# LooRollSensorTop.net
KiCad netlist of a schematic drawn in EAGLE
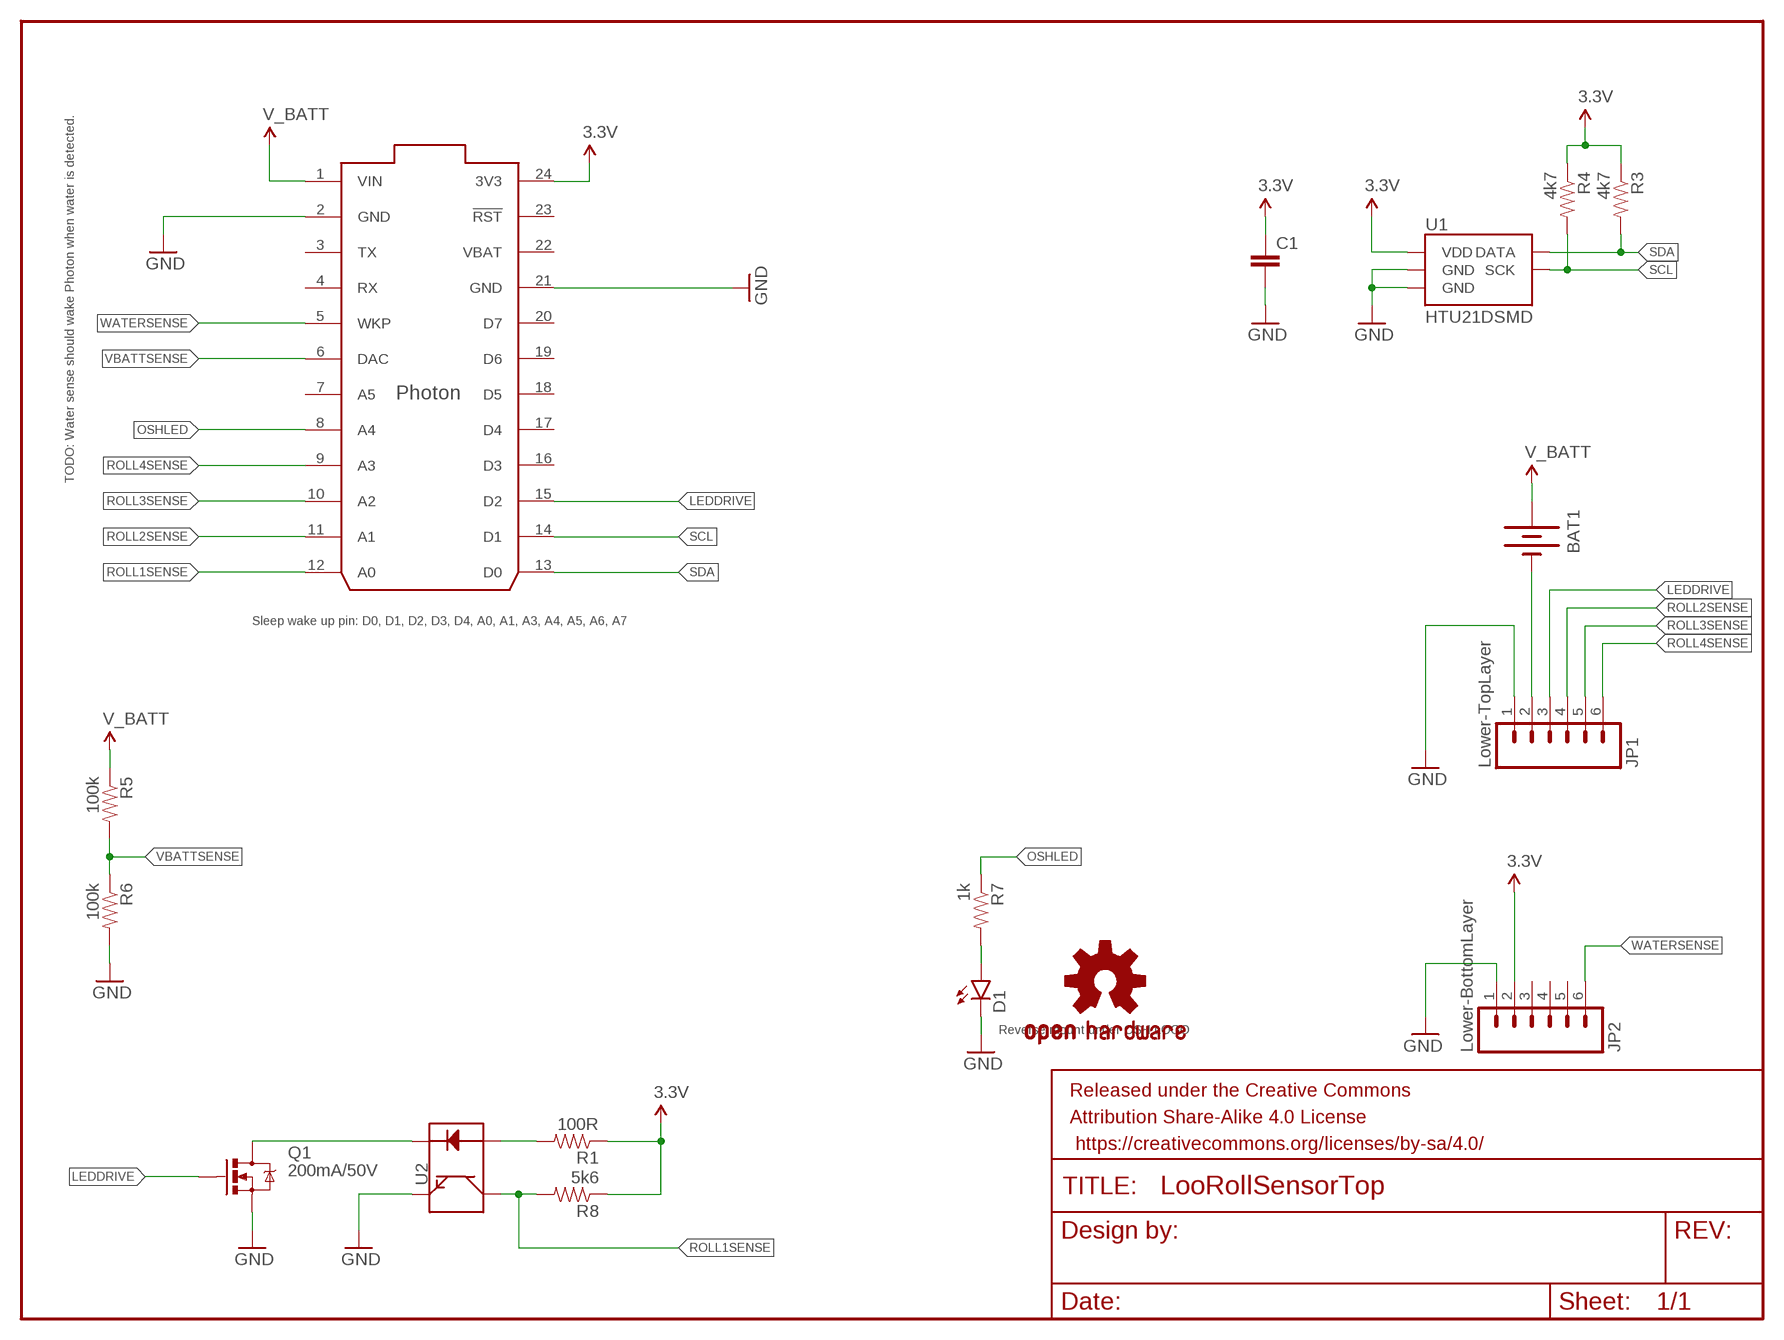
[diagram p0: schematic, sheet 1]

(export (version "E")
  (design (tool "Eeschema 10.0.6"))
  (components
    (comp (ref "BAT1")
      (value "BATTERYAA-PANEL")
      (footprint "eagle-import:BATTERY-AA-PANEL")
      (libsource (lib "eagle-import") (part "BATTERYAA-PANEL"))
    )
    (comp (ref "C1")
      (value "CAP0805")
      (footprint "eagle-import:0805")
      (libsource (lib "eagle-import") (part "CAP0805"))
    )
    (comp (ref "D1")
      (value "LED1206-BOTTOM")
      (footprint "eagle-import:LED-1206-BOTTOM")
      (libsource (lib "eagle-import") (part "LED1206-BOTTOM"))
    )
    (comp (ref "FRAME1")
      (value "FRAME-LETTER")
      (footprint "eagle-import:CREATIVE_COMMONS")
      (libsource (lib "eagle-import") (part "FRAME-LETTER"))
    )
    (comp (ref "JP1")
      (value "Lower-TopLayer")
      (footprint "eagle-import:1X06-SMD_EDGE")
      (libsource (lib "eagle-import") (part "M061X06-SMD-EDGE-SOLDERLINK1X06-SMD-EDGE-SOLDERLINK"))
    )
    (comp (ref "JP2")
      (value "Lower-BottomLayer")
      (footprint "eagle-import:1X06-SMD_EDGE")
      (libsource (lib "eagle-import") (part "M061X06-SMD-EDGE-SOLDERLINK1X06-SMD-EDGE-SOLDERLINK"))
    )
    (comp (ref "LOGO1")
      (value "OSHW-LOGOM")
      (footprint "eagle-import:OSHW-LOGO-M")
      (libsource (lib "eagle-import") (part "OSHW-LOGOM"))
    )
    (comp (ref "Q1")
      (value "200mA/50V")
      (footprint "eagle-import:SOT23-3")
      (libsource (lib "eagle-import") (part "MOSFET-NCHANNELBSS138"))
    )
    (comp (ref "R1")
      (value "100R")
      (footprint "eagle-import:1206")
      (libsource (lib "eagle-import") (part "RESISTOR1206"))
    )
    (comp (ref "R3")
      (value "4k7")
      (footprint "eagle-import:1206")
      (libsource (lib "eagle-import") (part "RESISTOR1206"))
    )
    (comp (ref "R4")
      (value "4k7")
      (footprint "eagle-import:1206")
      (libsource (lib "eagle-import") (part "RESISTOR1206"))
    )
    (comp (ref "R5")
      (value "100k")
      (footprint "eagle-import:1206")
      (libsource (lib "eagle-import") (part "RESISTOR1206"))
    )
    (comp (ref "R6")
      (value "100k")
      (footprint "eagle-import:1206")
      (libsource (lib "eagle-import") (part "RESISTOR1206"))
    )
    (comp (ref "R7")
      (value "1k")
      (footprint "eagle-import:1206")
      (libsource (lib "eagle-import") (part "RESISTOR1206"))
    )
    (comp (ref "R8")
      (value "5k6")
      (footprint "eagle-import:1206")
      (libsource (lib "eagle-import") (part "RESISTOR1206"))
    )
    (comp (ref "U$1")
      (value "PHOTON_WITH_HEADERS")
      (footprint "eagle-import:PHOTON")
      (libsource (lib "eagle-import") (part "PHOTON_WITH_HEADERS"))
    )
    (comp (ref "U1")
      (value "HTU21DSMD")
      (footprint "eagle-import:HTU21D")
      (libsource (lib "eagle-import") (part "HTU21DSMD"))
    )
    (comp (ref "U2")
      (value "QRE1113SMD-W")
      (footprint "eagle-import:QRE1113-W")
      (libsource (lib "eagle-import") (part "QRE1113SMD-W"))
    )
  )
  (nets
    (net (code "1") (name "/VBAT") (class "Default")
      (node (ref "U$1") (pin "22") (pinfunction "VBAT_22") (pintype "power_in"))
    )
    (net (code "2") (name "3.3V") (class "Default")
      (node (ref "C1") (pin "1") (pinfunction "1_1") (pintype "passive"))
      (node (ref "JP2") (pin "2") (pinfunction "2_2") (pintype "passive"))
      (node (ref "R1") (pin "1") (pinfunction "1_1") (pintype "passive"))
      (node (ref "R3") (pin "1") (pinfunction "1_1") (pintype "passive"))
      (node (ref "R4") (pin "1") (pinfunction "1_1") (pintype "passive"))
      (node (ref "R8") (pin "1") (pinfunction "1_1") (pintype "passive"))
      (node (ref "U$1") (pin "24") (pinfunction "3V3_24") (pintype "power_in"))
      (node (ref "U1") (pin "VDD") (pinfunction "VDD_VDD") (pintype "power_in"))
    )
    (net (code "3") (name "GND") (class "Default")
      (node (ref "C1") (pin "2") (pinfunction "2_2") (pintype "passive"))
      (node (ref "D1") (pin "C") (pinfunction "C_C") (pintype "passive"))
      (node (ref "JP1") (pin "1") (pinfunction "1_1") (pintype "passive"))
      (node (ref "JP2") (pin "1") (pinfunction "1_1") (pintype "passive"))
      (node (ref "Q1") (pin "2") (pinfunction "S_2") (pintype "passive"))
      (node (ref "R6") (pin "2") (pinfunction "2_2") (pintype "passive"))
      (node (ref "U$1") (pin "2") (pinfunction "GND_2") (pintype "power_in"))
      (node (ref "U$1") (pin "21") (pinfunction "GND_21") (pintype "power_in"))
      (node (ref "U1") (pin "7") (pinfunction "GND_7") (pintype "power_in"))
      (node (ref "U1") (pin "GND") (pinfunction "GND_GND") (pintype "power_in"))
      (node (ref "U2") (pin "4") (pinfunction "E_4") (pintype "bidirectional"))
    )
    (net (code "4") (name "LEDDRIVE") (class "Default")
      (node (ref "JP1") (pin "3") (pinfunction "3_3") (pintype "passive"))
      (node (ref "Q1") (pin "1") (pinfunction "G_1") (pintype "passive"))
      (node (ref "U$1") (pin "15") (pinfunction "D2_15") (pintype "bidirectional"))
    )
    (net (code "5") (name "Net-(BAT1-Pad-)") (class "Default")
      (node (ref "BAT1") (pin "-") (pinfunction "-_-") (pintype "power_in"))
      (node (ref "JP1") (pin "2") (pinfunction "2_2") (pintype "passive"))
    )
    (net (code "6") (name "Net-(D1-PadA)") (class "Default")
      (node (ref "D1") (pin "A") (pinfunction "A_A") (pintype "passive"))
      (node (ref "R7") (pin "2") (pinfunction "2_2") (pintype "passive"))
    )
    (net (code "7") (name "Net-(Q1-D)") (class "Default")
      (node (ref "Q1") (pin "3") (pinfunction "D_3") (pintype "passive"))
      (node (ref "U2") (pin "2") (pinfunction "K_2") (pintype "bidirectional"))
    )
    (net (code "8") (name "Net-(U2-A)") (class "Default")
      (node (ref "R1") (pin "2") (pinfunction "2_2") (pintype "passive"))
      (node (ref "U2") (pin "1") (pinfunction "A_1") (pintype "bidirectional"))
    )
    (net (code "9") (name "OSHLED") (class "Default")
      (node (ref "R7") (pin "1") (pinfunction "1_1") (pintype "passive"))
      (node (ref "U$1") (pin "8") (pinfunction "A4_8") (pintype "bidirectional"))
    )
    (net (code "10") (name "ROLL1SENSE") (class "Default")
      (node (ref "R8") (pin "2") (pinfunction "2_2") (pintype "passive"))
      (node (ref "U$1") (pin "12") (pinfunction "A0_12") (pintype "bidirectional"))
      (node (ref "U2") (pin "3") (pinfunction "C_3") (pintype "bidirectional"))
    )
    (net (code "11") (name "ROLL2SENSE") (class "Default")
      (node (ref "JP1") (pin "4") (pinfunction "4_4") (pintype "passive"))
      (node (ref "U$1") (pin "11") (pinfunction "A1_11") (pintype "bidirectional"))
    )
    (net (code "12") (name "ROLL3SENSE") (class "Default")
      (node (ref "JP1") (pin "5") (pinfunction "5_5") (pintype "passive"))
      (node (ref "U$1") (pin "10") (pinfunction "A2_10") (pintype "bidirectional"))
    )
    (net (code "13") (name "ROLL4SENSE") (class "Default")
      (node (ref "JP1") (pin "6") (pinfunction "6_6") (pintype "passive"))
      (node (ref "U$1") (pin "9") (pinfunction "A3_9") (pintype "bidirectional"))
    )
    (net (code "14") (name "SCL") (class "Default")
      (node (ref "R4") (pin "2") (pinfunction "2_2") (pintype "passive"))
      (node (ref "U$1") (pin "14") (pinfunction "D1_14") (pintype "bidirectional"))
      (node (ref "U1") (pin "SCK") (pinfunction "SCK_SCK") (pintype "input"))
    )
    (net (code "15") (name "SDA") (class "Default")
      (node (ref "R3") (pin "2") (pinfunction "2_2") (pintype "passive"))
      (node (ref "U$1") (pin "13") (pinfunction "D0_13") (pintype "bidirectional"))
      (node (ref "U1") (pin "DATA") (pinfunction "DATA_DATA") (pintype "bidirectional"))
    )
    (net (code "16") (name "VBATTSENSE") (class "Default")
      (node (ref "R5") (pin "2") (pinfunction "2_2") (pintype "passive"))
      (node (ref "R6") (pin "1") (pinfunction "1_1") (pintype "passive"))
      (node (ref "U$1") (pin "6") (pinfunction "DAC_6") (pintype "bidirectional"))
    )
    (net (code "17") (name "V_BATT") (class "Default")
      (node (ref "BAT1") (pin "+") (pinfunction "+_+") (pintype "power_in"))
      (node (ref "R5") (pin "1") (pinfunction "1_1") (pintype "passive"))
      (node (ref "U$1") (pin "1") (pinfunction "VIN_1") (pintype "power_in"))
    )
    (net (code "18") (name "WATERSENSE") (class "Default")
      (node (ref "JP2") (pin "6") (pinfunction "6_6") (pintype "passive"))
      (node (ref "U$1") (pin "5") (pinfunction "WKP_5") (pintype "bidirectional"))
    )
    (net (code "19") (name "unconnected-(JP2-Pad3)") (class "Default")
      (node (ref "JP2") (pin "3") (pinfunction "3_3") (pintype "passive"))
    )
    (net (code "20") (name "unconnected-(JP2-Pad4)") (class "Default")
      (node (ref "JP2") (pin "4") (pinfunction "4_4") (pintype "passive"))
    )
    (net (code "21") (name "unconnected-(JP2-Pad5)") (class "Default")
      (node (ref "JP2") (pin "5") (pinfunction "5_5") (pintype "passive"))
    )
    (net (code "22") (name "unconnected-(U$1-A5-Pad7)") (class "Default")
      (node (ref "U$1") (pin "7") (pinfunction "A5_7") (pintype "bidirectional"))
    )
    (net (code "23") (name "unconnected-(U$1-D3-Pad16)") (class "Default")
      (node (ref "U$1") (pin "16") (pinfunction "D3_16") (pintype "bidirectional"))
    )
    (net (code "24") (name "unconnected-(U$1-D4-Pad17)") (class "Default")
      (node (ref "U$1") (pin "17") (pinfunction "D4_17") (pintype "bidirectional"))
    )
    (net (code "25") (name "unconnected-(U$1-D5-Pad18)") (class "Default")
      (node (ref "U$1") (pin "18") (pinfunction "D5_18") (pintype "bidirectional"))
    )
    (net (code "26") (name "unconnected-(U$1-D6-Pad19)") (class "Default")
      (node (ref "U$1") (pin "19") (pinfunction "D6_19") (pintype "bidirectional"))
    )
    (net (code "27") (name "unconnected-(U$1-D7-Pad20)") (class "Default")
      (node (ref "U$1") (pin "20") (pinfunction "D7_20") (pintype "bidirectional"))
    )
    (net (code "28") (name "unconnected-(U$1-RX-Pad4)") (class "Default")
      (node (ref "U$1") (pin "4") (pinfunction "RX_4") (pintype "bidirectional"))
    )
    (net (code "29") (name "unconnected-(U$1-TX-Pad3)") (class "Default")
      (node (ref "U$1") (pin "3") (pinfunction "TX_3") (pintype "bidirectional"))
    )
    (net (code "30") (name "unconnected-(U$1-~{RST}-Pad23)") (class "Default")
      (node (ref "U$1") (pin "23") (pinfunction "~{RST}_23") (pintype "bidirectional"))
    )
  )
)
